# OSWarrior_Mini.net
KiCad netlist of a schematic drawn in EAGLE
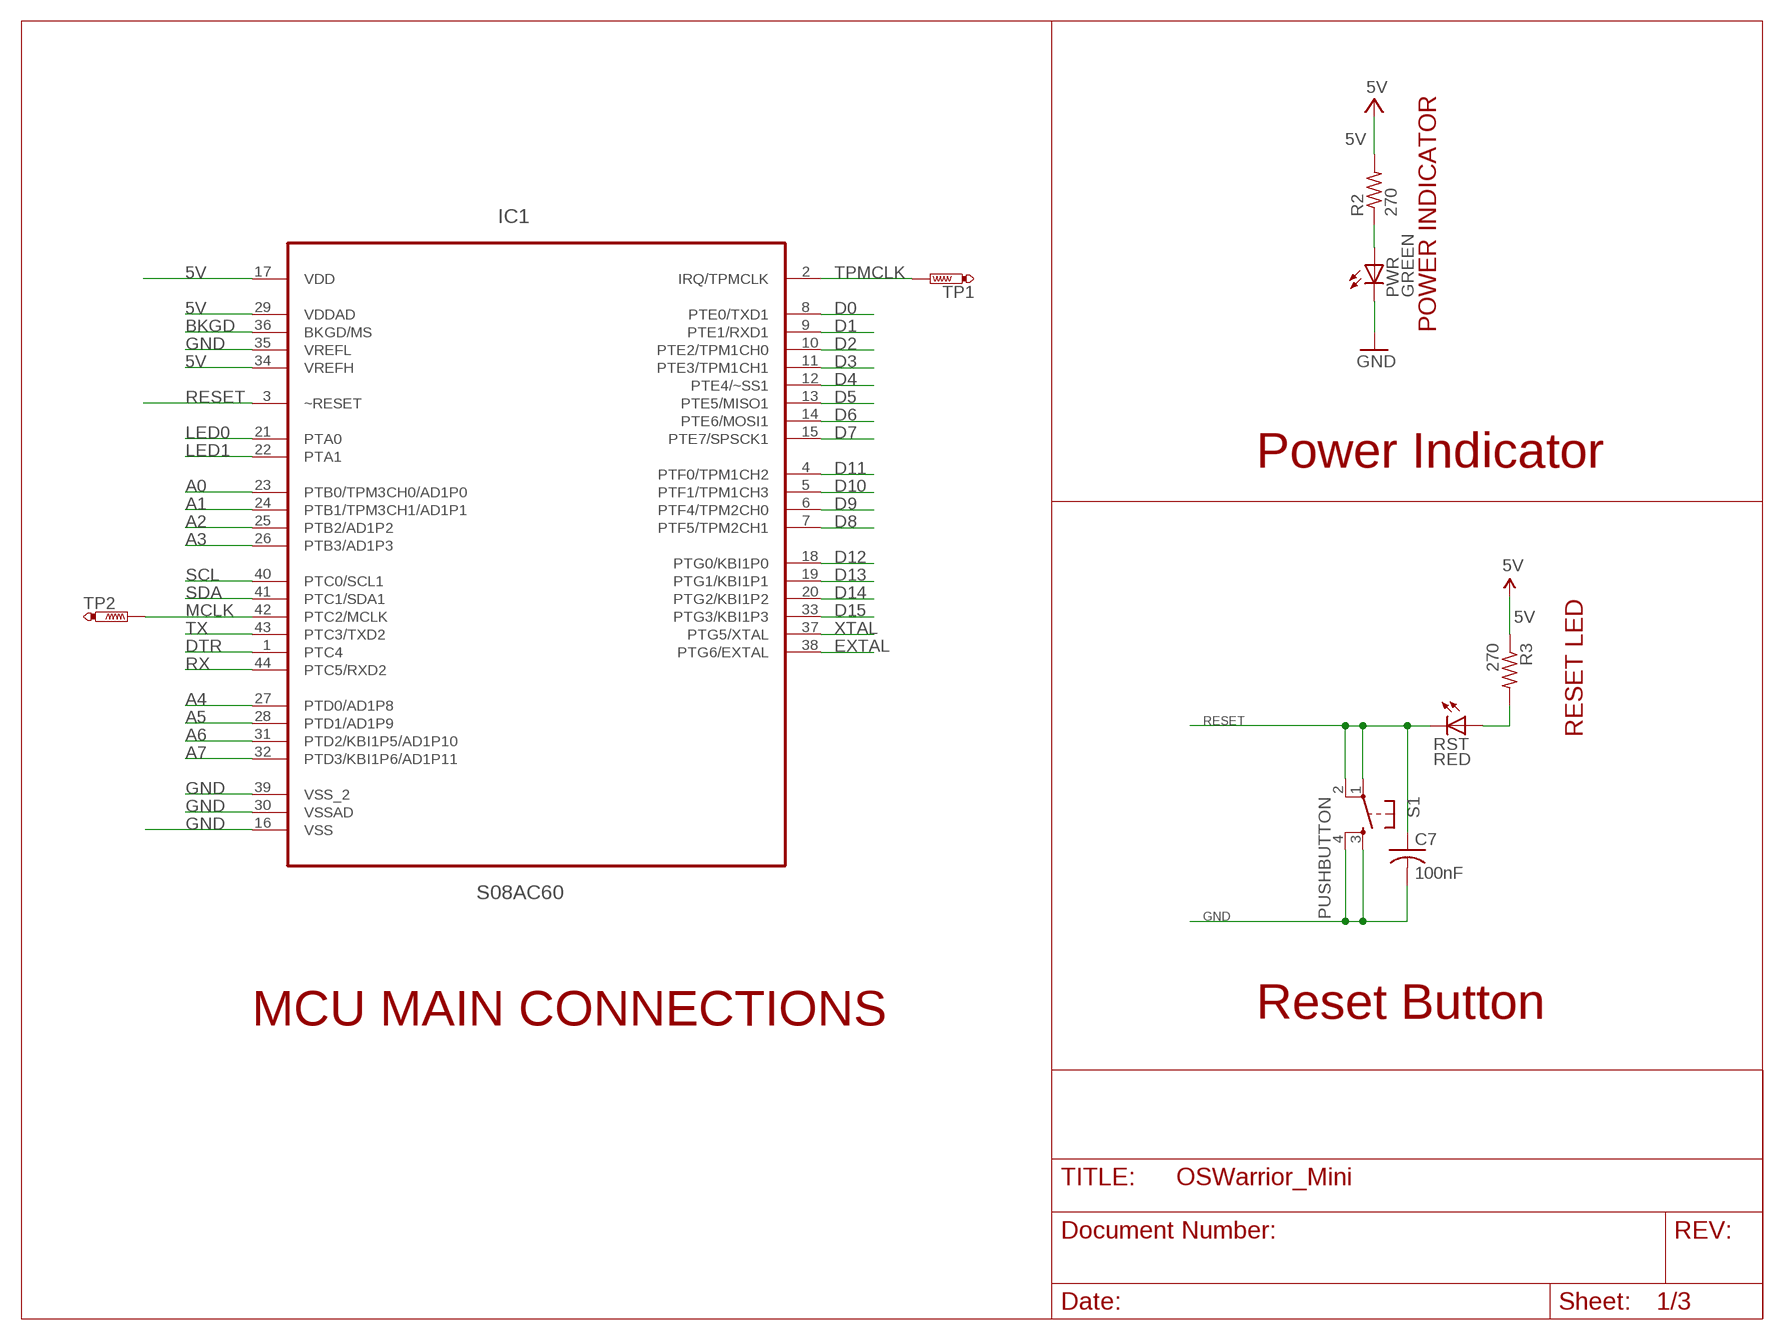
[diagram p0: schematic, sheet 1]
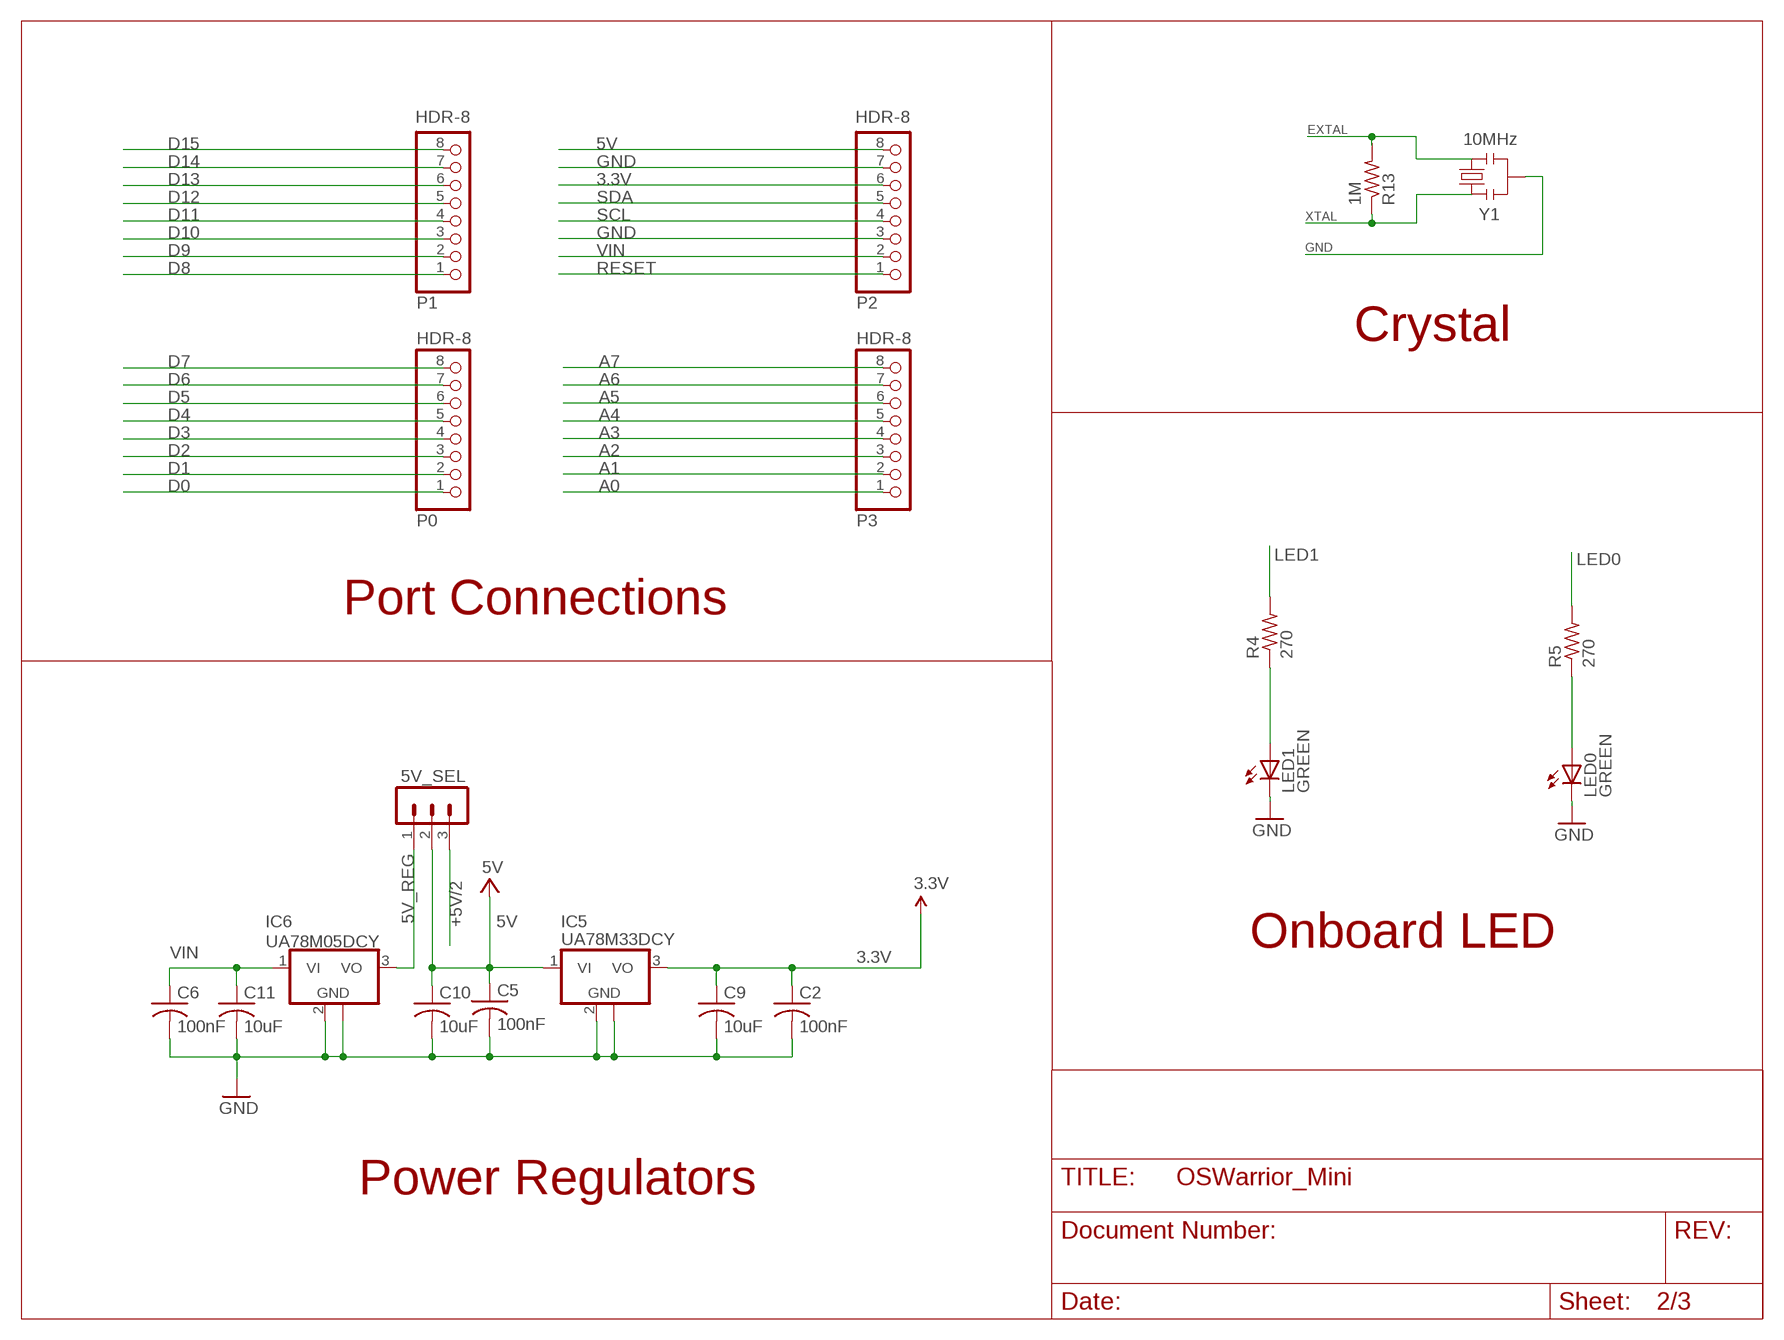
[diagram p1: schematic, sheet 2]
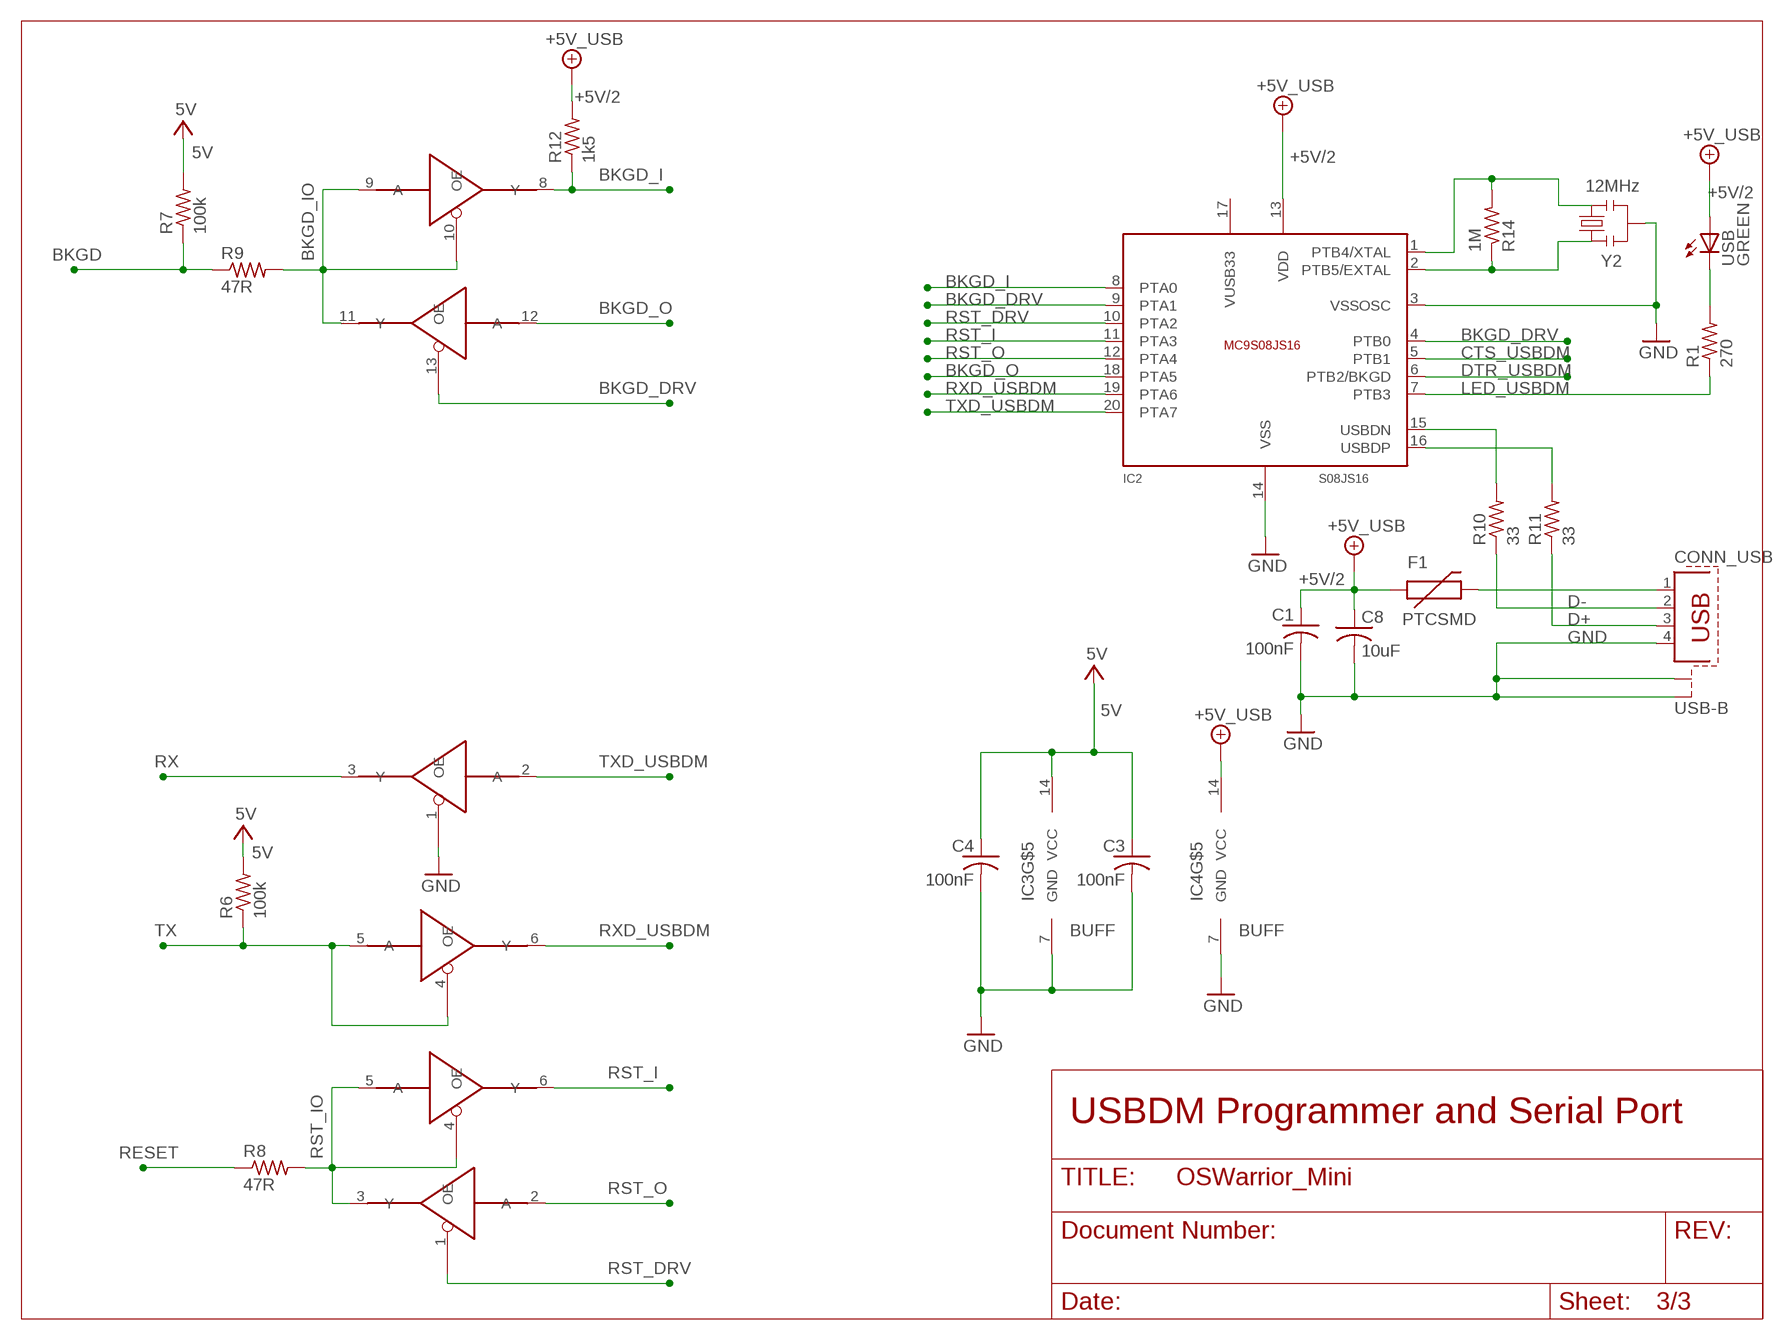
[diagram p2: schematic, sheet 3]

(export (version "E")
  (design (tool "Eeschema 10.0.6"))
  (components
    (comp (ref "C7")
      (value "100nF")
      (footprint "eagle-import:C0805")
      (libsource (lib "eagle-import") (part "C-USC0805"))
    )
    (comp (ref "IC1")
      (value "S08AC60")
      (footprint "eagle-import:LQFP-44")
      (libsource (lib "eagle-import") (part "MC9S08AC48CFGE_LQFP-44"))
    )
    (comp (ref "PWR")
      (value "GREEN")
      (footprint "eagle-import:CHIPLED_1206")
      (libsource (lib "eagle-import") (part "LEDCHIPLED_1206"))
    )
    (comp (ref "R2")
      (value "270")
      (footprint "eagle-import:M0805")
      (libsource (lib "eagle-import") (part "R-US_M0805"))
    )
    (comp (ref "R3")
      (value "270")
      (footprint "eagle-import:M0805")
      (libsource (lib "eagle-import") (part "R-US_M0805"))
    )
    (comp (ref "RST")
      (value "RED")
      (footprint "eagle-import:CHIPLED_1206")
      (libsource (lib "eagle-import") (part "LEDCHIPLED_1206"))
    )
    (comp (ref "S1")
      (value "PUSHBUTTON")
      (footprint "eagle-import:TACTILE-PTH")
      (libsource (lib "eagle-import") (part "TAC_SWITCHPTH"))
    )
    (comp (ref "TP1")
      (value "PTR1B1,27")
      (footprint "eagle-import:B1,27")
      (libsource (lib "eagle-import") (part "PTR1B1,27"))
    )
    (comp (ref "TP2")
      (value "PTR1B1,27")
      (footprint "eagle-import:B1,27")
      (libsource (lib "eagle-import") (part "PTR1B1,27"))
    )
    (comp (ref "5V_SEL")
      (value "J1")
      (footprint "eagle-import:MA03-1")
      (libsource (lib "eagle-import") (part "MA03-1"))
    )
    (comp (ref "C2")
      (value "100nF")
      (footprint "eagle-import:C0805")
      (libsource (lib "eagle-import") (part "C-USC0805"))
    )
    (comp (ref "C5")
      (value "100nF")
      (footprint "eagle-import:C0805")
      (libsource (lib "eagle-import") (part "C-USC0805"))
    )
    (comp (ref "C6")
      (value "100nF")
      (footprint "eagle-import:C0805")
      (libsource (lib "eagle-import") (part "C-USC0805"))
    )
    (comp (ref "C9")
      (value "10uF")
      (footprint "eagle-import:C0805")
      (libsource (lib "eagle-import") (part "C-USC0805"))
    )
    (comp (ref "C10")
      (value "10uF")
      (footprint "eagle-import:C0805")
      (libsource (lib "eagle-import") (part "C-USC0805"))
    )
    (comp (ref "C11")
      (value "10uF")
      (footprint "eagle-import:C0805")
      (libsource (lib "eagle-import") (part "C-USC0805"))
    )
    (comp (ref "IC5")
      (value "UA78M33DCY")
      (footprint "eagle-import:SOT223")
      (libsource (lib "eagle-import") (part "UA78MDCY33"))
    )
    (comp (ref "IC6")
      (value "UA78M05DCY")
      (footprint "eagle-import:SOT223")
      (libsource (lib "eagle-import") (part "UA78MDCY05"))
    )
    (comp (ref "LED0")
      (value "GREEN")
      (footprint "eagle-import:CHIPLED_1206")
      (libsource (lib "eagle-import") (part "LEDCHIPLED_1206"))
    )
    (comp (ref "LED1")
      (value "GREEN")
      (footprint "eagle-import:CHIPLED_1206")
      (libsource (lib "eagle-import") (part "LEDCHIPLED_1206"))
    )
    (comp (ref "P0")
      (value "HDR-8")
      (footprint "eagle-import:1X08")
      (libsource (lib "eagle-import") (part "PINHD-1X8"))
    )
    (comp (ref "P1")
      (value "HDR-8")
      (footprint "eagle-import:1X08")
      (libsource (lib "eagle-import") (part "PINHD-1X8"))
    )
    (comp (ref "P2")
      (value "HDR-8")
      (footprint "eagle-import:1X08")
      (libsource (lib "eagle-import") (part "PINHD-1X8"))
    )
    (comp (ref "P3")
      (value "HDR-8")
      (footprint "eagle-import:1X08")
      (libsource (lib "eagle-import") (part "PINHD-1X8"))
    )
    (comp (ref "R4")
      (value "270")
      (footprint "eagle-import:M0805")
      (libsource (lib "eagle-import") (part "R-US_M0805"))
    )
    (comp (ref "R5")
      (value "270")
      (footprint "eagle-import:M0805")
      (libsource (lib "eagle-import") (part "R-US_M0805"))
    )
    (comp (ref "R13")
      (value "1M")
      (footprint "eagle-import:M0805")
      (libsource (lib "eagle-import") (part "R-US_M0805"))
    )
    (comp (ref "Y1")
      (value "10MHz")
      (footprint "eagle-import:RESONATOR-SMD")
      (libsource (lib "eagle-import") (part "RESONATORSMD"))
    )
    (comp (ref "C1")
      (value "100nF")
      (footprint "eagle-import:C0805")
      (libsource (lib "eagle-import") (part "C-USC0805"))
    )
    (comp (ref "C3")
      (value "100nF")
      (footprint "eagle-import:C0805")
      (libsource (lib "eagle-import") (part "C-USC0805"))
    )
    (comp (ref "C4")
      (value "100nF")
      (footprint "eagle-import:C0805")
      (libsource (lib "eagle-import") (part "C-USC0805"))
    )
    (comp (ref "C8")
      (value "10uF")
      (footprint "eagle-import:C0805")
      (libsource (lib "eagle-import") (part "C-USC0805"))
    )
    (comp (ref "CONN_USB")
      (value "USB-B")
      (footprint "eagle-import:PN61729-S")
      (libsource (lib "eagle-import") (part "PN61729-S"))
    )
    (comp (ref "F1")
      (value "PTCSMD")
      (footprint "eagle-import:PTC-1206")
      (libsource (lib "eagle-import") (part "PTCSMD"))
    )
    (comp (ref "IC2")
      (value "S08JS16")
      (footprint "eagle-import:SOIC-20")
      (libsource (lib "eagle-import") (part "MC9S08JS16CWJ_SOIC-20"))
    )
    (comp (ref "IC3")
      (value "BUFF")
      (footprint "eagle-import:TSSOP-14")
      (libsource (lib "eagle-import") (part "SN74LV125APW_TSSOP-14"))
    )
    (comp (ref "IC4")
      (value "BUFF")
      (footprint "eagle-import:TSSOP-14")
      (libsource (lib "eagle-import") (part "SN74LV125APW_TSSOP-14"))
    )
    (comp (ref "R1")
      (value "270")
      (footprint "eagle-import:M0805")
      (libsource (lib "eagle-import") (part "R-US_M0805"))
    )
    (comp (ref "R6")
      (value "100k")
      (footprint "eagle-import:M0805")
      (libsource (lib "eagle-import") (part "R-US_M0805"))
    )
    (comp (ref "R7")
      (value "100k")
      (footprint "eagle-import:M0805")
      (libsource (lib "eagle-import") (part "R-US_M0805"))
    )
    (comp (ref "R8")
      (value "47R")
      (footprint "eagle-import:M0805")
      (libsource (lib "eagle-import") (part "R-US_M0805"))
    )
    (comp (ref "R9")
      (value "47R")
      (footprint "eagle-import:M0805")
      (libsource (lib "eagle-import") (part "R-US_M0805"))
    )
    (comp (ref "R10")
      (value "33")
      (footprint "eagle-import:M0805")
      (libsource (lib "eagle-import") (part "R-US_M0805"))
    )
    (comp (ref "R11")
      (value "33")
      (footprint "eagle-import:M0805")
      (libsource (lib "eagle-import") (part "R-US_M0805"))
    )
    (comp (ref "R12")
      (value "1k5")
      (footprint "eagle-import:M0805")
      (libsource (lib "eagle-import") (part "R-US_M0805"))
    )
    (comp (ref "R14")
      (value "1M")
      (footprint "eagle-import:M0805")
      (libsource (lib "eagle-import") (part "R-US_M0805"))
    )
    (comp (ref "USB")
      (value "GREEN")
      (footprint "eagle-import:CHIPLED_1206")
      (libsource (lib "eagle-import") (part "LEDCHIPLED_1206"))
    )
    (comp (ref "Y2")
      (value "12MHz")
      (footprint "eagle-import:RESONATOR-SMD")
      (libsource (lib "eagle-import") (part "RESONATORSMD"))
    )
  )
  (nets
    (net (code "1") (name "+5V{slash}2") (class "Default")
      (node (ref "5V_SEL") (pin "3") (pinfunction "3_3") (pintype "passive"))
      (node (ref "C1") (pin "1") (pinfunction "1_1") (pintype "passive"))
      (node (ref "C8") (pin "1") (pinfunction "1_1") (pintype "passive"))
      (node (ref "F1") (pin "1") (pinfunction "1_1") (pintype "bidirectional"))
      (node (ref "IC2") (pin "13") (pinfunction "VDD_13") (pintype "power_in"))
      (node (ref "IC4") (pin "14") (pinfunction "VCC_14") (pintype "power_in"))
      (node (ref "R12") (pin "2") (pinfunction "2_2") (pintype "passive"))
      (node (ref "USB") (pin "A") (pinfunction "A_A") (pintype "passive"))
    )
    (net (code "2") (name "3.3V") (class "Default")
      (node (ref "C2") (pin "1") (pinfunction "1_1") (pintype "passive"))
      (node (ref "C9") (pin "1") (pinfunction "1_1") (pintype "passive"))
      (node (ref "IC5") (pin "3") (pinfunction "VO_3") (pintype "passive"))
      (node (ref "P2") (pin "6") (pinfunction "6_6") (pintype "passive"))
    )
    (net (code "3") (name "5V") (class "Default")
      (node (ref "5V_SEL") (pin "2") (pinfunction "2_2") (pintype "passive"))
      (node (ref "C10") (pin "1") (pinfunction "1_1") (pintype "passive"))
      (node (ref "C3") (pin "1") (pinfunction "1_1") (pintype "passive"))
      (node (ref "C4") (pin "1") (pinfunction "1_1") (pintype "passive"))
      (node (ref "C5") (pin "1") (pinfunction "1_1") (pintype "passive"))
      (node (ref "IC1") (pin "17") (pinfunction "VDD_17") (pintype "power_in"))
      (node (ref "IC1") (pin "29") (pinfunction "VDDAD_29") (pintype "power_in"))
      (node (ref "IC1") (pin "34") (pinfunction "VREFH_34") (pintype "input"))
      (node (ref "IC3") (pin "14") (pinfunction "VCC_14") (pintype "power_in"))
      (node (ref "IC5") (pin "1") (pinfunction "VI_1") (pintype "input"))
      (node (ref "P2") (pin "8") (pinfunction "8_8") (pintype "passive"))
      (node (ref "R2") (pin "2") (pinfunction "2_2") (pintype "passive"))
      (node (ref "R3") (pin "1") (pinfunction "1_1") (pintype "passive"))
      (node (ref "R6") (pin "2") (pinfunction "2_2") (pintype "passive"))
      (node (ref "R7") (pin "2") (pinfunction "2_2") (pintype "passive"))
    )
    (net (code "4") (name "5V_REG") (class "Default")
      (node (ref "5V_SEL") (pin "1") (pinfunction "1_1") (pintype "passive"))
      (node (ref "IC6") (pin "3") (pinfunction "VO_3") (pintype "passive"))
    )
    (net (code "5") (name "A0") (class "Default")
      (node (ref "IC1") (pin "23") (pinfunction "PTB0/TPM3CH0/AD1P0_23") (pintype "bidirectional"))
      (node (ref "P3") (pin "1") (pinfunction "1_1") (pintype "passive"))
    )
    (net (code "6") (name "A1") (class "Default")
      (node (ref "IC1") (pin "24") (pinfunction "PTB1/TPM3CH1/AD1P1_24") (pintype "bidirectional"))
      (node (ref "P3") (pin "2") (pinfunction "2_2") (pintype "passive"))
    )
    (net (code "7") (name "A2") (class "Default")
      (node (ref "IC1") (pin "25") (pinfunction "PTB2/AD1P2_25") (pintype "bidirectional"))
      (node (ref "P3") (pin "3") (pinfunction "3_3") (pintype "passive"))
    )
    (net (code "8") (name "A3") (class "Default")
      (node (ref "IC1") (pin "26") (pinfunction "PTB3/AD1P3_26") (pintype "bidirectional"))
      (node (ref "P3") (pin "4") (pinfunction "4_4") (pintype "passive"))
    )
    (net (code "9") (name "A4") (class "Default")
      (node (ref "IC1") (pin "27") (pinfunction "PTD0/AD1P8_27") (pintype "bidirectional"))
      (node (ref "P3") (pin "5") (pinfunction "5_5") (pintype "passive"))
    )
    (net (code "10") (name "A5") (class "Default")
      (node (ref "IC1") (pin "28") (pinfunction "PTD1/AD1P9_28") (pintype "bidirectional"))
      (node (ref "P3") (pin "6") (pinfunction "6_6") (pintype "passive"))
    )
    (net (code "11") (name "A6") (class "Default")
      (node (ref "IC1") (pin "31") (pinfunction "PTD2/KBI1P5/AD1P10_31") (pintype "bidirectional"))
      (node (ref "P3") (pin "7") (pinfunction "7_7") (pintype "passive"))
    )
    (net (code "12") (name "A7") (class "Default")
      (node (ref "IC1") (pin "32") (pinfunction "PTD3/KBI1P6/AD1P11_32") (pintype "bidirectional"))
      (node (ref "P3") (pin "8") (pinfunction "8_8") (pintype "passive"))
    )
    (net (code "13") (name "BKGD") (class "Default")
      (node (ref "IC1") (pin "36") (pinfunction "BKGD/MS_36") (pintype "bidirectional"))
      (node (ref "R7") (pin "1") (pinfunction "1_1") (pintype "passive"))
      (node (ref "R9") (pin "1") (pinfunction "1_1") (pintype "passive"))
    )
    (net (code "14") (name "BKGD_DRV") (class "Default")
      (node (ref "IC2") (pin "4") (pinfunction "PTB0_4") (pintype "bidirectional"))
      (node (ref "IC2") (pin "9") (pinfunction "PTA1_9") (pintype "bidirectional"))
      (node (ref "IC4") (pin "13") (pinfunction "OE_13") (pintype "input"))
    )
    (net (code "15") (name "BKGD_I") (class "Default")
      (node (ref "IC2") (pin "8") (pinfunction "PTA0_8") (pintype "bidirectional"))
      (node (ref "IC4") (pin "8") (pinfunction "Y_8") (pintype "output"))
      (node (ref "R12") (pin "1") (pinfunction "1_1") (pintype "passive"))
    )
    (net (code "16") (name "BKGD_IO") (class "Default")
      (node (ref "IC4") (pin "10") (pinfunction "OE_10") (pintype "input"))
      (node (ref "IC4") (pin "11") (pinfunction "Y_11") (pintype "output"))
      (node (ref "IC4") (pin "9") (pinfunction "A_9") (pintype "input"))
      (node (ref "R9") (pin "2") (pinfunction "2_2") (pintype "passive"))
    )
    (net (code "17") (name "BKGD_O") (class "Default")
      (node (ref "IC2") (pin "18") (pinfunction "PTA5_18") (pintype "bidirectional"))
      (node (ref "IC4") (pin "12") (pinfunction "A_12") (pintype "input"))
    )
    (net (code "18") (name "CTS_USBDM") (class "Default")
      (node (ref "IC2") (pin "5") (pinfunction "PTB1_5") (pintype "bidirectional"))
    )
    (net (code "19") (name "D+") (class "Default")
      (node (ref "CONN_USB") (pin "3") (pinfunction "3_3") (pintype "passive"))
      (node (ref "R11") (pin "1") (pinfunction "1_1") (pintype "passive"))
    )
    (net (code "20") (name "D-") (class "Default")
      (node (ref "CONN_USB") (pin "2") (pinfunction "2_2") (pintype "passive"))
      (node (ref "R10") (pin "1") (pinfunction "1_1") (pintype "passive"))
    )
    (net (code "21") (name "D0") (class "Default")
      (node (ref "IC1") (pin "8") (pinfunction "PTE0/TXD1_8") (pintype "bidirectional"))
      (node (ref "P0") (pin "1") (pinfunction "1_1") (pintype "passive"))
    )
    (net (code "22") (name "D1") (class "Default")
      (node (ref "IC1") (pin "9") (pinfunction "PTE1/RXD1_9") (pintype "bidirectional"))
      (node (ref "P0") (pin "2") (pinfunction "2_2") (pintype "passive"))
    )
    (net (code "23") (name "D2") (class "Default")
      (node (ref "IC1") (pin "10") (pinfunction "PTE2/TPM1CH0_10") (pintype "bidirectional"))
      (node (ref "P0") (pin "3") (pinfunction "3_3") (pintype "passive"))
    )
    (net (code "24") (name "D3") (class "Default")
      (node (ref "IC1") (pin "11") (pinfunction "PTE3/TPM1CH1_11") (pintype "bidirectional"))
      (node (ref "P0") (pin "4") (pinfunction "4_4") (pintype "passive"))
    )
    (net (code "25") (name "D4") (class "Default")
      (node (ref "IC1") (pin "12") (pinfunction "PTE4/~{SS1}_12") (pintype "bidirectional"))
      (node (ref "P0") (pin "5") (pinfunction "5_5") (pintype "passive"))
    )
    (net (code "26") (name "D5") (class "Default")
      (node (ref "IC1") (pin "13") (pinfunction "PTE5/MISO1_13") (pintype "bidirectional"))
      (node (ref "P0") (pin "6") (pinfunction "6_6") (pintype "passive"))
    )
    (net (code "27") (name "D6") (class "Default")
      (node (ref "IC1") (pin "14") (pinfunction "PTE6/MOSI1_14") (pintype "bidirectional"))
      (node (ref "P0") (pin "7") (pinfunction "7_7") (pintype "passive"))
    )
    (net (code "28") (name "D7") (class "Default")
      (node (ref "IC1") (pin "15") (pinfunction "PTE7/SPSCK1_15") (pintype "bidirectional"))
      (node (ref "P0") (pin "8") (pinfunction "8_8") (pintype "passive"))
    )
    (net (code "29") (name "D8") (class "Default")
      (node (ref "IC1") (pin "7") (pinfunction "PTF5/TPM2CH1_7") (pintype "bidirectional"))
      (node (ref "P1") (pin "1") (pinfunction "1_1") (pintype "passive"))
    )
    (net (code "30") (name "D9") (class "Default")
      (node (ref "IC1") (pin "6") (pinfunction "PTF4/TPM2CH0_6") (pintype "bidirectional"))
      (node (ref "P1") (pin "2") (pinfunction "2_2") (pintype "passive"))
    )
    (net (code "31") (name "D10") (class "Default")
      (node (ref "IC1") (pin "5") (pinfunction "PTF1/TPM1CH3_5") (pintype "bidirectional"))
      (node (ref "P1") (pin "3") (pinfunction "3_3") (pintype "passive"))
    )
    (net (code "32") (name "D11") (class "Default")
      (node (ref "IC1") (pin "4") (pinfunction "PTF0/TPM1CH2_4") (pintype "bidirectional"))
      (node (ref "P1") (pin "4") (pinfunction "4_4") (pintype "passive"))
    )
    (net (code "33") (name "D12") (class "Default")
      (node (ref "IC1") (pin "18") (pinfunction "PTG0/KBI1P0_18") (pintype "bidirectional"))
      (node (ref "P1") (pin "5") (pinfunction "5_5") (pintype "passive"))
    )
    (net (code "34") (name "D13") (class "Default")
      (node (ref "IC1") (pin "19") (pinfunction "PTG1/KBI1P1_19") (pintype "bidirectional"))
      (node (ref "P1") (pin "6") (pinfunction "6_6") (pintype "passive"))
    )
    (net (code "35") (name "D14") (class "Default")
      (node (ref "IC1") (pin "20") (pinfunction "PTG2/KBI1P2_20") (pintype "bidirectional"))
      (node (ref "P1") (pin "7") (pinfunction "7_7") (pintype "passive"))
    )
    (net (code "36") (name "D15") (class "Default")
      (node (ref "IC1") (pin "33") (pinfunction "PTG3/KBI1P3_33") (pintype "bidirectional"))
      (node (ref "P1") (pin "8") (pinfunction "8_8") (pintype "passive"))
    )
    (net (code "37") (name "DTR") (class "Default")
      (node (ref "IC1") (pin "1") (pinfunction "PTC4_1") (pintype "bidirectional"))
    )
    (net (code "38") (name "DTR_USBDM") (class "Default")
      (node (ref "IC2") (pin "6") (pinfunction "PTB2/BKGD_6") (pintype "bidirectional"))
    )
    (net (code "39") (name "EXTAL") (class "Default")
      (node (ref "IC1") (pin "38") (pinfunction "PTG6/EXTAL_38") (pintype "bidirectional"))
      (node (ref "R13") (pin "2") (pinfunction "2_2") (pintype "passive"))
      (node (ref "Y1") (pin "3") (pinfunction "3_3") (pintype "passive"))
    )
    (net (code "40") (name "GND") (class "Default")
      (node (ref "C1") (pin "2") (pinfunction "2_2") (pintype "passive"))
      (node (ref "C10") (pin "2") (pinfunction "2_2") (pintype "passive"))
      (node (ref "C11") (pin "2") (pinfunction "2_2") (pintype "passive"))
      (node (ref "C2") (pin "2") (pinfunction "2_2") (pintype "passive"))
      (node (ref "C3") (pin "2") (pinfunction "2_2") (pintype "passive"))
      (node (ref "C4") (pin "2") (pinfunction "2_2") (pintype "passive"))
      (node (ref "C5") (pin "2") (pinfunction "2_2") (pintype "passive"))
      (node (ref "C6") (pin "2") (pinfunction "2_2") (pintype "passive"))
      (node (ref "C7") (pin "2") (pinfunction "2_2") (pintype "passive"))
      (node (ref "C8") (pin "2") (pinfunction "2_2") (pintype "passive"))
      (node (ref "C9") (pin "2") (pinfunction "2_2") (pintype "passive"))
      (node (ref "CONN_USB") (pin "4") (pinfunction "4_4") (pintype "passive"))
      (node (ref "CONN_USB") (pin "S1") (pinfunction "S1_S1") (pintype "passive"))
      (node (ref "CONN_USB") (pin "S2") (pinfunction "S2_S2") (pintype "passive"))
      (node (ref "IC1") (pin "16") (pinfunction "VSS_16") (pintype "power_in"))
      (node (ref "IC1") (pin "30") (pinfunction "VSSAD_30") (pintype "power_in"))
      (node (ref "IC1") (pin "35") (pinfunction "VREFL_35") (pintype "input"))
      (node (ref "IC1") (pin "39") (pinfunction "VSS_2_39") (pintype "power_in"))
      (node (ref "IC2") (pin "14") (pinfunction "VSS_14") (pintype "power_in"))
      (node (ref "IC2") (pin "3") (pinfunction "VSSOSC_3") (pintype "power_in"))
      (node (ref "IC3") (pin "1") (pinfunction "OE_1") (pintype "input"))
      (node (ref "IC3") (pin "7") (pinfunction "GND_7") (pintype "power_in"))
      (node (ref "IC4") (pin "7") (pinfunction "GND_7") (pintype "power_in"))
      (node (ref "IC5") (pin "2") (pinfunction "GND_2") (pintype "passive"))
      (node (ref "IC5") (pin "4") (pinfunction "GND_4") (pintype "passive"))
      (node (ref "IC6") (pin "2") (pinfunction "GND_2") (pintype "passive"))
      (node (ref "IC6") (pin "4") (pinfunction "GND_4") (pintype "passive"))
      (node (ref "LED0") (pin "C") (pinfunction "C_C") (pintype "passive"))
      (node (ref "LED1") (pin "C") (pinfunction "C_C") (pintype "passive"))
      (node (ref "P2") (pin "3") (pinfunction "3_3") (pintype "passive"))
      (node (ref "P2") (pin "7") (pinfunction "7_7") (pintype "passive"))
      (node (ref "PWR") (pin "C") (pinfunction "C_C") (pintype "passive"))
      (node (ref "S1") (pin "3") (pinfunction "3_3") (pintype "passive"))
      (node (ref "S1") (pin "4") (pinfunction "4_4") (pintype "passive"))
      (node (ref "Y1") (pin "2") (pinfunction "2_2") (pintype "passive"))
      (node (ref "Y2") (pin "2") (pinfunction "2_2") (pintype "passive"))
    )
    (net (code "41") (name "LED0") (class "Default")
      (node (ref "IC1") (pin "21") (pinfunction "PTA0_21") (pintype "bidirectional"))
      (node (ref "R5") (pin "2") (pinfunction "2_2") (pintype "passive"))
    )
    (net (code "42") (name "LED1") (class "Default")
      (node (ref "IC1") (pin "22") (pinfunction "PTA1_22") (pintype "bidirectional"))
      (node (ref "R4") (pin "2") (pinfunction "2_2") (pintype "passive"))
    )
    (net (code "43") (name "LED_USBDM") (class "Default")
      (node (ref "IC2") (pin "7") (pinfunction "PTB3_7") (pintype "bidirectional"))
      (node (ref "R1") (pin "1") (pinfunction "1_1") (pintype "passive"))
    )
    (net (code "44") (name "MCLK") (class "Default")
      (node (ref "IC1") (pin "42") (pinfunction "PTC2/MCLK_42") (pintype "bidirectional"))
      (node (ref "TP2") (pin "TP") (pinfunction "TP_TP") (pintype "input"))
    )
    (net (code "45") (name "Net-(CONN_USB-Pad1)") (class "Default")
      (node (ref "CONN_USB") (pin "1") (pinfunction "1_1") (pintype "passive"))
      (node (ref "F1") (pin "2") (pinfunction "2_2") (pintype "bidirectional"))
    )
    (net (code "46") (name "Net-(IC2-PTB4{slash}XTAL)") (class "Default")
      (node (ref "IC2") (pin "1") (pinfunction "PTB4/XTAL_1") (pintype "bidirectional"))
      (node (ref "R14") (pin "2") (pinfunction "2_2") (pintype "passive"))
      (node (ref "Y2") (pin "3") (pinfunction "3_3") (pintype "passive"))
    )
    (net (code "47") (name "Net-(IC2-PTB5{slash}EXTAL)") (class "Default")
      (node (ref "IC2") (pin "2") (pinfunction "PTB5/EXTAL_2") (pintype "bidirectional"))
      (node (ref "R14") (pin "1") (pinfunction "1_1") (pintype "passive"))
      (node (ref "Y2") (pin "1") (pinfunction "1_1") (pintype "passive"))
    )
    (net (code "48") (name "Net-(IC2-USBDN)") (class "Default")
      (node (ref "IC2") (pin "15") (pinfunction "USBDN_15") (pintype "bidirectional"))
      (node (ref "R10") (pin "2") (pinfunction "2_2") (pintype "passive"))
    )
    (net (code "49") (name "Net-(IC2-USBDP)") (class "Default")
      (node (ref "IC2") (pin "16") (pinfunction "USBDP_16") (pintype "bidirectional"))
      (node (ref "R11") (pin "2") (pinfunction "2_2") (pintype "passive"))
    )
    (net (code "50") (name "Net-(LED0-PadA)") (class "Default")
      (node (ref "LED0") (pin "A") (pinfunction "A_A") (pintype "passive"))
      (node (ref "R5") (pin "1") (pinfunction "1_1") (pintype "passive"))
    )
    (net (code "51") (name "Net-(LED1-PadA)") (class "Default")
      (node (ref "LED1") (pin "A") (pinfunction "A_A") (pintype "passive"))
      (node (ref "R4") (pin "1") (pinfunction "1_1") (pintype "passive"))
    )
    (net (code "52") (name "Net-(PWR-PadA)") (class "Default")
      (node (ref "PWR") (pin "A") (pinfunction "A_A") (pintype "passive"))
      (node (ref "R2") (pin "1") (pinfunction "1_1") (pintype "passive"))
    )
    (net (code "53") (name "Net-(R1-Pad2)") (class "Default")
      (node (ref "R1") (pin "2") (pinfunction "2_2") (pintype "passive"))
      (node (ref "USB") (pin "C") (pinfunction "C_C") (pintype "passive"))
    )
    (net (code "54") (name "Net-(R3-Pad2)") (class "Default")
      (node (ref "R3") (pin "2") (pinfunction "2_2") (pintype "passive"))
      (node (ref "RST") (pin "A") (pinfunction "A_A") (pintype "passive"))
    )
    (net (code "55") (name "RESET") (class "Default")
      (node (ref "C7") (pin "1") (pinfunction "1_1") (pintype "passive"))
      (node (ref "IC1") (pin "3") (pinfunction "~{RESET}_3") (pintype "input"))
      (node (ref "P2") (pin "1") (pinfunction "1_1") (pintype "passive"))
      (node (ref "R8") (pin "1") (pinfunction "1_1") (pintype "passive"))
      (node (ref "RST") (pin "C") (pinfunction "C_C") (pintype "passive"))
      (node (ref "S1") (pin "1") (pinfunction "1_1") (pintype "passive"))
      (node (ref "S1") (pin "2") (pinfunction "2_2") (pintype "passive"))
    )
    (net (code "56") (name "RST_DRV") (class "Default")
      (node (ref "IC2") (pin "10") (pinfunction "PTA2_10") (pintype "bidirectional"))
      (node (ref "IC4") (pin "1") (pinfunction "OE_1") (pintype "input"))
    )
    (net (code "57") (name "RST_I") (class "Default")
      (node (ref "IC2") (pin "11") (pinfunction "PTA3_11") (pintype "bidirectional"))
      (node (ref "IC4") (pin "6") (pinfunction "Y_6") (pintype "output"))
    )
    (net (code "58") (name "RST_IO") (class "Default")
      (node (ref "IC4") (pin "3") (pinfunction "Y_3") (pintype "output"))
      (node (ref "IC4") (pin "4") (pinfunction "OE_4") (pintype "input"))
      (node (ref "IC4") (pin "5") (pinfunction "A_5") (pintype "input"))
      (node (ref "R8") (pin "2") (pinfunction "2_2") (pintype "passive"))
    )
    (net (code "59") (name "RST_O") (class "Default")
      (node (ref "IC2") (pin "12") (pinfunction "PTA4_12") (pintype "bidirectional"))
      (node (ref "IC4") (pin "2") (pinfunction "A_2") (pintype "input"))
    )
    (net (code "60") (name "RX") (class "Default")
      (node (ref "IC1") (pin "44") (pinfunction "PTC5/RXD2_44") (pintype "bidirectional"))
      (node (ref "IC3") (pin "3") (pinfunction "Y_3") (pintype "output"))
    )
    (net (code "61") (name "RXD_USBDM") (class "Default")
      (node (ref "IC2") (pin "19") (pinfunction "PTA6_19") (pintype "bidirectional"))
      (node (ref "IC3") (pin "6") (pinfunction "Y_6") (pintype "output"))
    )
    (net (code "62") (name "SCL") (class "Default")
      (node (ref "IC1") (pin "40") (pinfunction "PTC0/SCL1_40") (pintype "bidirectional"))
      (node (ref "P2") (pin "4") (pinfunction "4_4") (pintype "passive"))
    )
    (net (code "63") (name "SDA") (class "Default")
      (node (ref "IC1") (pin "41") (pinfunction "PTC1/SDA1_41") (pintype "bidirectional"))
      (node (ref "P2") (pin "5") (pinfunction "5_5") (pintype "passive"))
    )
    (net (code "64") (name "TPMCLK") (class "Default")
      (node (ref "IC1") (pin "2") (pinfunction "IRQ/TPMCLK_2") (pintype "bidirectional"))
      (node (ref "TP1") (pin "TP") (pinfunction "TP_TP") (pintype "input"))
    )
    (net (code "65") (name "TX") (class "Default")
      (node (ref "IC1") (pin "43") (pinfunction "PTC3/TXD2_43") (pintype "bidirectional"))
      (node (ref "IC3") (pin "4") (pinfunction "OE_4") (pintype "input"))
      (node (ref "IC3") (pin "5") (pinfunction "A_5") (pintype "input"))
      (node (ref "R6") (pin "1") (pinfunction "1_1") (pintype "passive"))
    )
    (net (code "66") (name "TXD_USBDM") (class "Default")
      (node (ref "IC2") (pin "20") (pinfunction "PTA7_20") (pintype "bidirectional"))
      (node (ref "IC3") (pin "2") (pinfunction "A_2") (pintype "input"))
    )
    (net (code "67") (name "VIN") (class "Default")
      (node (ref "C11") (pin "1") (pinfunction "1_1") (pintype "passive"))
      (node (ref "C6") (pin "1") (pinfunction "1_1") (pintype "passive"))
      (node (ref "IC6") (pin "1") (pinfunction "VI_1") (pintype "input"))
      (node (ref "P2") (pin "2") (pinfunction "2_2") (pintype "passive"))
    )
    (net (code "68") (name "VUSB33") (class "Default")
      (node (ref "IC2") (pin "17") (pinfunction "VUSB33_17") (pintype "power_in"))
    )
    (net (code "69") (name "XTAL") (class "Default")
      (node (ref "IC1") (pin "37") (pinfunction "PTG5/XTAL_37") (pintype "bidirectional"))
      (node (ref "R13") (pin "1") (pinfunction "1_1") (pintype "passive"))
      (node (ref "Y1") (pin "1") (pinfunction "1_1") (pintype "passive"))
    )
  )
)
